# 09_CAN.net
KiCad netlist of a schematic drawn in Altium Designer
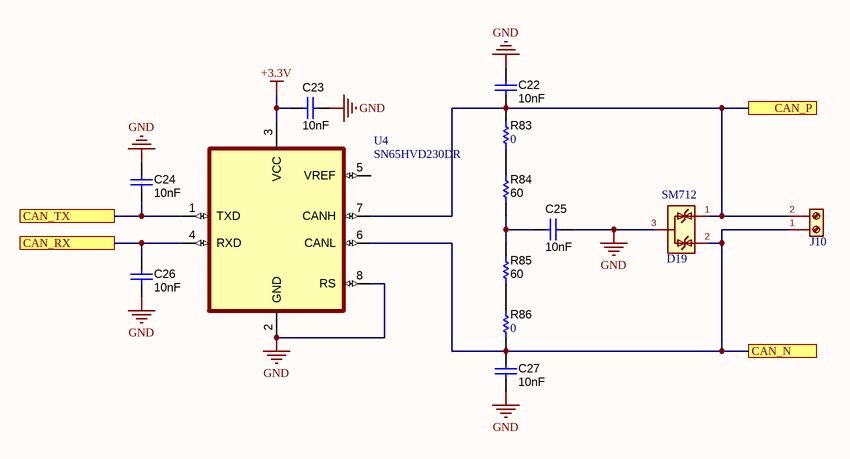
[diagram p0: 09_CAN.SchDoc]

(export (version "E")
  (design (tool "Eeschema 10.0.6"))
  (components
    (comp (ref "C22")
      (value "CAP 10nF 0603")
      (footprint "0603")
      (description "CAP, CERM, 10 nF, 50 V, +/- 10%, X7R, AEC-Q200 Grade 1, 0603")
      (fields
        (field (name "MANUFACTURER") "MuRata")
        (field (name "PARTNUMBER") "GCM188R70J225KE22D")
        (field (name "VALUEDISPLAYED") "10nF")
        (field (name "PUBLISHER") "Texas Instruments")
      )
      (libsource (lib "PROC051C_AWR1843BOOST_RevC") (part "CAP 10nF 0603"))
    )
    (comp (ref "C23")
      (value "CAP 10nF 0603")
      (footprint "0603")
      (description "CAP, CERM, 10 nF, 50 V, +/- 10%, X7R, AEC-Q200 Grade 1, 0603")
      (fields
        (field (name "MANUFACTURER") "MuRata")
        (field (name "PARTNUMBER") "GCM188R70J225KE22D")
        (field (name "VALUEDISPLAYED") "10nF")
        (field (name "PUBLISHER") "Texas Instruments")
      )
      (libsource (lib "PROC051C_AWR1843BOOST_RevC") (part "CAP 10nF 0603"))
    )
    (comp (ref "C24")
      (value "CAP 10nF 0603")
      (footprint "0603")
      (description "CAP, CERM, 10 nF, 50 V, +/- 10%, X7R, AEC-Q200 Grade 1, 0603")
      (fields
        (field (name "MANUFACTURER") "MuRata")
        (field (name "PARTNUMBER") "GCM188R70J225KE22D")
        (field (name "VALUEDISPLAYED") "10nF")
        (field (name "PUBLISHER") "Texas Instruments")
      )
      (libsource (lib "PROC051C_AWR1843BOOST_RevC") (part "CAP 10nF 0603"))
    )
    (comp (ref "C25")
      (value "CAP 10nF 0603")
      (footprint "0603")
      (description "CAP, CERM, 10 nF, 50 V, +/- 10%, X7R, AEC-Q200 Grade 1, 0603")
      (fields
        (field (name "MANUFACTURER") "MuRata")
        (field (name "PARTNUMBER") "GCM188R70J225KE22D")
        (field (name "VALUEDISPLAYED") "10nF")
        (field (name "PUBLISHER") "Texas Instruments")
      )
      (libsource (lib "PROC051C_AWR1843BOOST_RevC") (part "CAP 10nF 0603"))
    )
    (comp (ref "C26")
      (value "CAP 10nF 0603")
      (footprint "0603")
      (description "CAP, CERM, 10 nF, 50 V, +/- 10%, X7R, AEC-Q200 Grade 1, 0603")
      (fields
        (field (name "MANUFACTURER") "MuRata")
        (field (name "PARTNUMBER") "GCM188R70J225KE22D")
        (field (name "VALUEDISPLAYED") "10nF")
        (field (name "PUBLISHER") "Texas Instruments")
      )
      (libsource (lib "PROC051C_AWR1843BOOST_RevC") (part "CAP 10nF 0603"))
    )
    (comp (ref "C27")
      (value "CAP 10nF 0603")
      (footprint "0603")
      (description "CAP, CERM, 10 nF, 50 V, +/- 10%, X7R, AEC-Q200 Grade 1, 0603")
      (fields
        (field (name "MANUFACTURER") "MuRata")
        (field (name "PARTNUMBER") "GCM188R70J225KE22D")
        (field (name "VALUEDISPLAYED") "10nF")
        (field (name "PUBLISHER") "Texas Instruments")
      )
      (libsource (lib "PROC051C_AWR1843BOOST_RevC") (part "CAP 10nF 0603"))
    )
    (comp (ref "D19")
      (value "SM712")
      (footprint "SOT-23")
      (libsource (lib "PROC051C_AWR1843BOOST_RevC") (part "PESD5V0L2BT,215"))
    )
    (comp (ref "J10")
      (value "Terminal_01x02_P5.00")
      (footprint "TerminalBlock_Phoenix_PT-1,5-2-5.0-H_1x02_P5.00mm_Horizontal")
      (libsource (lib "PROC051C_AWR1843BOOST_RevC") (part "Terminal_01x02_P5.00"))
    )
    (comp (ref "R83")
      (value "ERJ-2GE0R00X")
      (footprint "0402L")
      (description "RES, 0, 5%, 0.1 W, AEC-Q200 Grade 0, 0402")
      (fields (field (name "MANUFACTURER") "Panasonic") (field (name "VALUEDISPLAYED") "0"))
      (libsource (lib "PROC051C_AWR1843BOOST_RevC") (part "RES 0R 0402 0.1W"))
    )
    (comp (ref "R84")
      (value "MCT06030Z0000ZP500")
      (footprint "0603")
      (description "RES, 60, 5%, 0.125 W, 0603")
      (fields
        (field (name "MANUFACTURER") "Vishay/Beyschlag")
        (field (name "VALUEDISPLAYED") "60")
        (field (name "PUBLISHER") "Texas Instruments")
      )
      (libsource (lib "PROC051C_AWR1843BOOST_RevC") (part "RES 60R 0603"))
    )
    (comp (ref "R85")
      (value "MCT06030Z0000ZP500")
      (footprint "0603")
      (description "RES, 60, 5%, 0.125 W, 0603")
      (fields
        (field (name "MANUFACTURER") "Vishay/Beyschlag")
        (field (name "VALUEDISPLAYED") "60")
        (field (name "PUBLISHER") "Texas Instruments")
      )
      (libsource (lib "PROC051C_AWR1843BOOST_RevC") (part "RES 60R 0603"))
    )
    (comp (ref "R86")
      (value "ERJ-2GE0R00X")
      (footprint "0402L")
      (description "RES, 0, 5%, 0.1 W, AEC-Q200 Grade 0, 0402")
      (fields (field (name "MANUFACTURER") "Panasonic") (field (name "VALUEDISPLAYED") "0"))
      (libsource (lib "PROC051C_AWR1843BOOST_RevC") (part "RES 0R 0402 0.1W"))
    )
    (comp (ref "U4")
      (value "SN65HVD230DR")
      (footprint "SOIC127P599X175-8N")
      (description "3.3-V CAN Transceivers")
      (fields (field (name "MF") "Texas Instruments") (field (name "MP") "TCAN332DR"))
      (libsource (lib "PROC051C_AWR1843BOOST_RevC") (part "SN65HVD230DR_1"))
    )
  )
  (nets
    (net (code "1") (name "+3.3V") (class "Default")
      (node (ref "C23") (pin "2") (pinfunction "2_2") (pintype "passive"))
      (node (ref "U4") (pin "3") (pinfunction "VCC_3") (pintype "power_in"))
    )
    (net (code "2") (name "/CAN_N") (class "Default")
      (node (ref "C27") (pin "1") (pinfunction "1_1") (pintype "passive"))
      (node (ref "D19") (pin "2") (pinfunction "K_2") (pintype "passive"))
      (node (ref "J10") (pin "1") (pinfunction "Pin_1_1") (pintype "passive"))
      (node (ref "R86") (pin "1") (pinfunction "1_1") (pintype "passive"))
      (node (ref "U4") (pin "6") (pinfunction "CANL_6") (pintype "bidirectional"))
    )
    (net (code "3") (name "/CAN_P") (class "Default")
      (node (ref "C22") (pin "2") (pinfunction "2_2") (pintype "passive"))
      (node (ref "D19") (pin "1") (pinfunction "K_1") (pintype "passive"))
      (node (ref "J10") (pin "2") (pinfunction "Pin_2_2") (pintype "passive"))
      (node (ref "R83") (pin "2") (pinfunction "2_2") (pintype "passive"))
      (node (ref "U4") (pin "7") (pinfunction "CANH_7") (pintype "bidirectional"))
    )
    (net (code "4") (name "/CAN_RX") (class "Default")
      (node (ref "C26") (pin "1") (pinfunction "1_1") (pintype "passive"))
      (node (ref "U4") (pin "4") (pinfunction "RXD_4") (pintype "bidirectional"))
    )
    (net (code "5") (name "/CAN_TX") (class "Default")
      (node (ref "C24") (pin "2") (pinfunction "2_2") (pintype "passive"))
      (node (ref "U4") (pin "1") (pinfunction "TXD_1") (pintype "bidirectional"))
    )
    (net (code "6") (name "GND") (class "Default")
      (node (ref "C22") (pin "1") (pinfunction "1_1") (pintype "passive"))
      (node (ref "C23") (pin "1") (pinfunction "1_1") (pintype "passive"))
      (node (ref "C24") (pin "1") (pinfunction "1_1") (pintype "passive"))
      (node (ref "C25") (pin "1") (pinfunction "1_1") (pintype "passive"))
      (node (ref "C26") (pin "2") (pinfunction "2_2") (pintype "passive"))
      (node (ref "C27") (pin "2") (pinfunction "2_2") (pintype "passive"))
      (node (ref "D19") (pin "3") (pinfunction "A_3") (pintype "passive"))
      (node (ref "U4") (pin "2") (pinfunction "GND_2") (pintype "power_in"))
      (node (ref "U4") (pin "8") (pinfunction "RS_8") (pintype "bidirectional"))
    )
    (net (code "7") (name "Net-(C25-Pad2)") (class "Default")
      (node (ref "C25") (pin "2") (pinfunction "2_2") (pintype "passive"))
      (node (ref "R84") (pin "1") (pinfunction "1_1") (pintype "passive"))
      (node (ref "R85") (pin "2") (pinfunction "2_2") (pintype "passive"))
    )
    (net (code "8") (name "Net-(R83-Pad1)") (class "Default")
      (node (ref "R83") (pin "1") (pinfunction "1_1") (pintype "passive"))
      (node (ref "R84") (pin "2") (pinfunction "2_2") (pintype "passive"))
    )
    (net (code "9") (name "Net-(R85-Pad1)") (class "Default")
      (node (ref "R85") (pin "1") (pinfunction "1_1") (pintype "passive"))
      (node (ref "R86") (pin "2") (pinfunction "2_2") (pintype "passive"))
    )
    (net (code "10") (name "unconnected-(U4-VREF-Pad5)") (class "Default")
      (node (ref "U4") (pin "5") (pinfunction "VREF_5") (pintype "bidirectional"))
    )
  )
)
